# Joystick.net
KiCad netlist of a schematic drawn in EAGLE
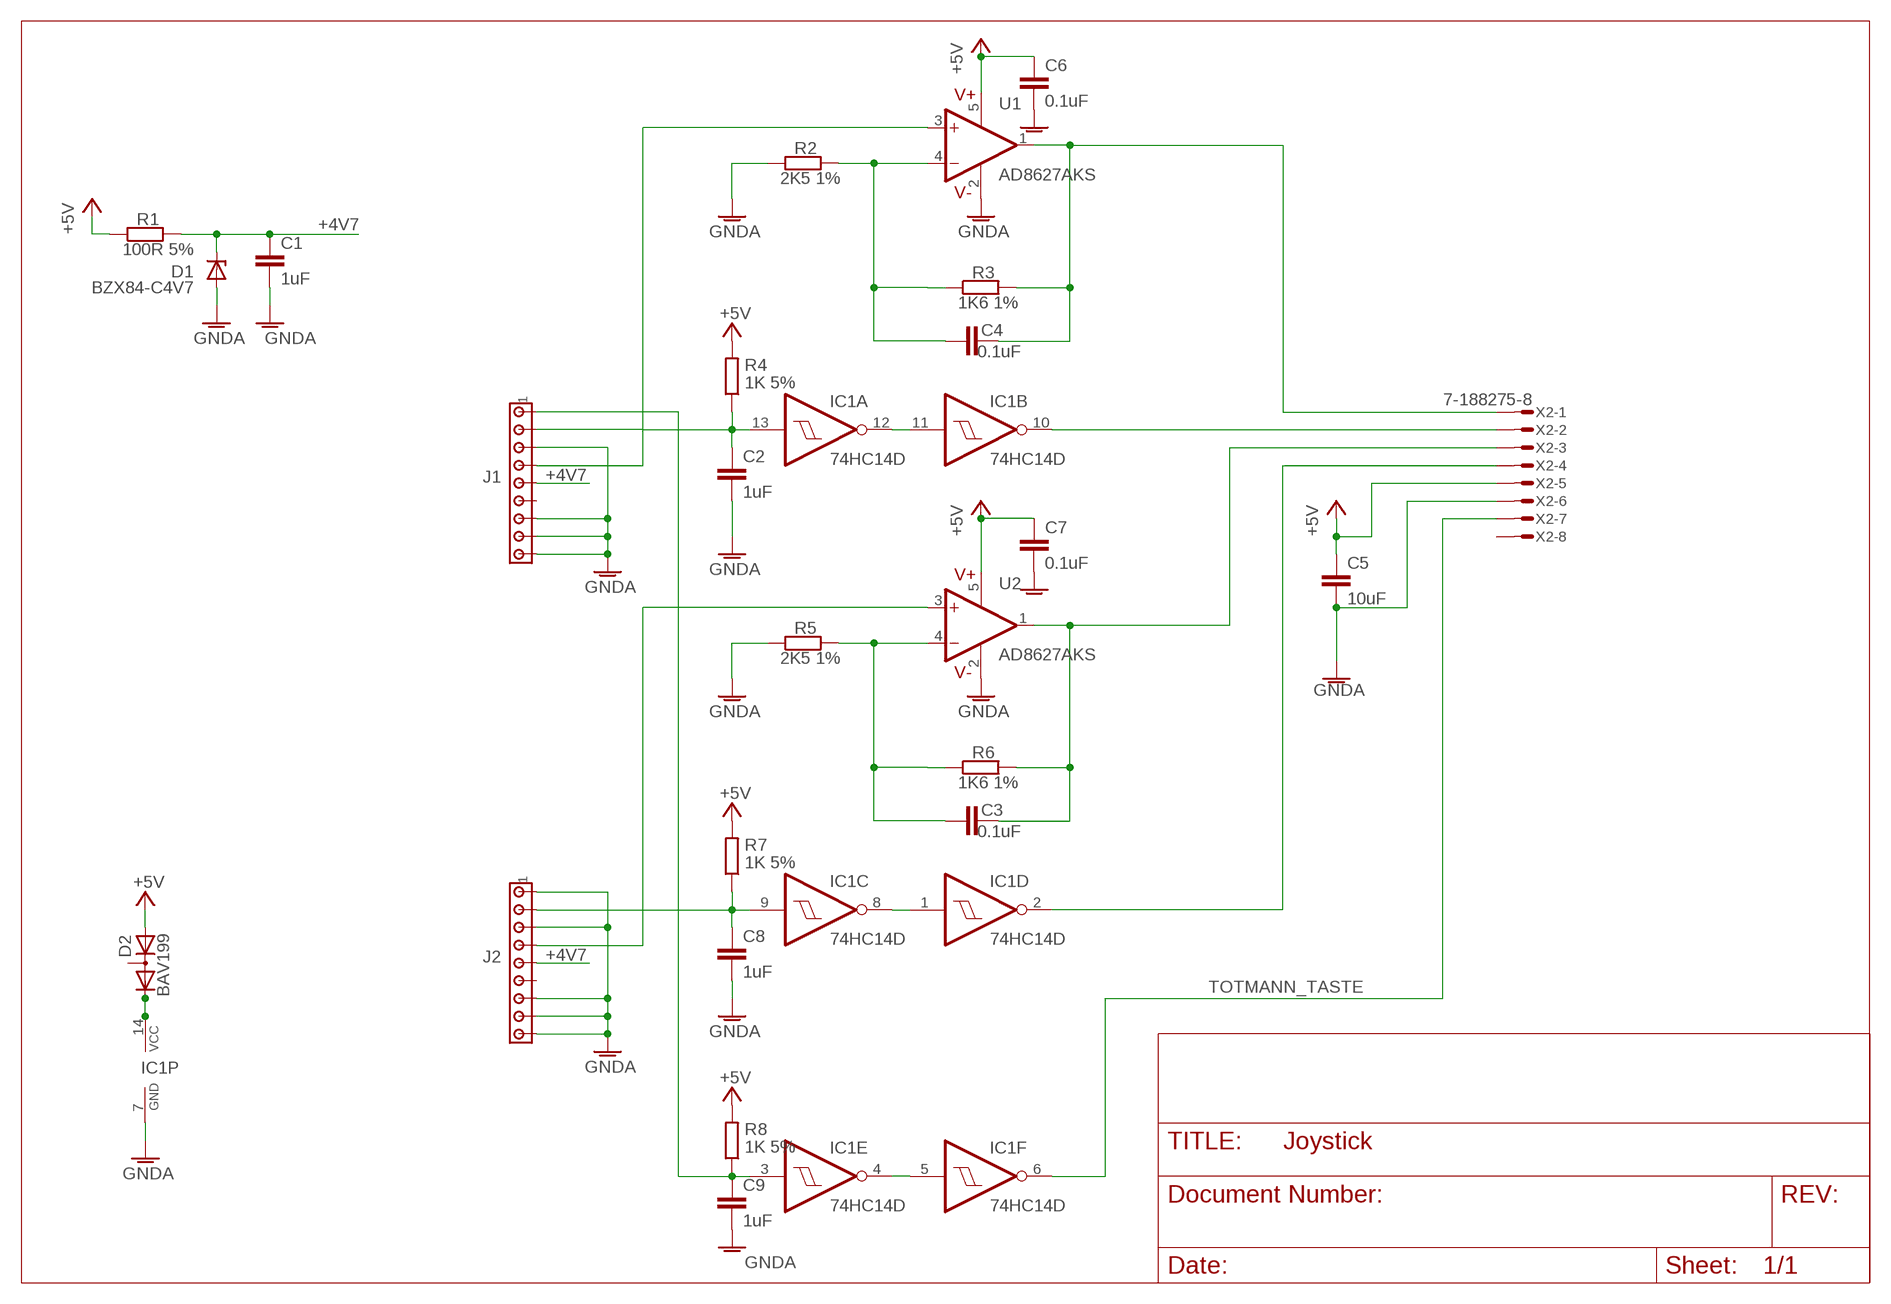
[diagram p0: schematic, sheet 1]

(export (version "E")
  (design (tool "Eeschema 10.0.6"))
  (components
    (comp (ref "C1")
      (value "1uF")
      (footprint "eagle-import:C0805")
      (libsource (lib "eagle-import") (part "C-EUC0805"))
    )
    (comp (ref "C2")
      (value "1uF")
      (footprint "eagle-import:C0805")
      (libsource (lib "eagle-import") (part "C-EUC0805"))
    )
    (comp (ref "C3")
      (value "0.1uF")
      (footprint "eagle-import:C0805")
      (libsource (lib "eagle-import") (part "C-EUC0805"))
    )
    (comp (ref "C4")
      (value "0.1uF")
      (footprint "eagle-import:C0805")
      (libsource (lib "eagle-import") (part "C-EUC0805"))
    )
    (comp (ref "C5")
      (value "10uF")
      (footprint "eagle-import:C0805")
      (libsource (lib "eagle-import") (part "C-EUC0805"))
    )
    (comp (ref "C6")
      (value "0.1uF")
      (footprint "eagle-import:C0805")
      (libsource (lib "eagle-import") (part "C-EUC0805"))
    )
    (comp (ref "C7")
      (value "0.1uF")
      (footprint "eagle-import:C0805")
      (libsource (lib "eagle-import") (part "C-EUC0805"))
    )
    (comp (ref "C8")
      (value "1uF")
      (footprint "eagle-import:C0805")
      (libsource (lib "eagle-import") (part "C-EUC0805"))
    )
    (comp (ref "C9")
      (value "1uF")
      (footprint "eagle-import:C0805")
      (libsource (lib "eagle-import") (part "C-EUC0805"))
    )
    (comp (ref "D1")
      (value "BZX84-C4V7")
      (footprint "eagle-import:SOT23")
      (libsource (lib "eagle-import") (part "ZENER-DIODESOT23"))
    )
    (comp (ref "D2")
      (value "BAV199")
      (footprint "eagle-import:SOT23")
      (libsource (lib "eagle-import") (part "BAV199"))
    )
    (comp (ref "IC1")
      (value "74HC14D")
      (footprint "eagle-import:SO14")
      (libsource (lib "eagle-import") (part "7414DHC"))
    )
    (comp (ref "J1")
      (value "MTA09-100")
      (footprint "eagle-import:10X09MTA")
      (libsource (lib "eagle-import") (part "MTA09-100"))
    )
    (comp (ref "J2")
      (value "MTA09-100")
      (footprint "eagle-import:10X09MTA")
      (libsource (lib "eagle-import") (part "MTA09-100"))
    )
    (comp (ref "R1")
      (value "100R 5%")
      (footprint "eagle-import:R0805")
      (libsource (lib "eagle-import") (part "R-EU_R0805"))
    )
    (comp (ref "R2")
      (value "2K5 1%")
      (footprint "eagle-import:R0805")
      (libsource (lib "eagle-import") (part "R-EU_R0805"))
    )
    (comp (ref "R3")
      (value "1K6 1%")
      (footprint "eagle-import:R0805")
      (libsource (lib "eagle-import") (part "R-EU_R0805"))
    )
    (comp (ref "R4")
      (value "1K 5%")
      (footprint "eagle-import:R0805")
      (libsource (lib "eagle-import") (part "R-EU_R0805"))
    )
    (comp (ref "R5")
      (value "2K5 1%")
      (footprint "eagle-import:R0805")
      (libsource (lib "eagle-import") (part "R-EU_R0805"))
    )
    (comp (ref "R6")
      (value "1K6 1%")
      (footprint "eagle-import:R0805")
      (libsource (lib "eagle-import") (part "R-EU_R0805"))
    )
    (comp (ref "R7")
      (value "1K 5%")
      (footprint "eagle-import:R0805")
      (libsource (lib "eagle-import") (part "R-EU_R0805"))
    )
    (comp (ref "R8")
      (value "1K 5%")
      (footprint "eagle-import:R0805")
      (libsource (lib "eagle-import") (part "R-EU_R0805"))
    )
    (comp (ref "U1")
      (value "AD8627AKS")
      (footprint "eagle-import:SC70(KS-5)")
      (libsource (lib "eagle-import") (part "AD8627AKS"))
    )
    (comp (ref "U2")
      (value "AD8627AKS")
      (footprint "eagle-import:SC70(KS-5)")
      (libsource (lib "eagle-import") (part "AD8627AKS"))
    )
    (comp (ref "X2")
      (value "7-188275-8")
      (footprint "eagle-import:MMT-F-SMD-8")
      (libsource (lib "eagle-import") (part "MICROMATCH-8SMF"))
    )
  )
  (nets
    (net (code "1") (name "+5V") (class "Default")
      (node (ref "C5") (pin "1") (pinfunction "1_1") (pintype "passive"))
      (node (ref "C6") (pin "1") (pinfunction "1_1") (pintype "passive"))
      (node (ref "C7") (pin "1") (pinfunction "1_1") (pintype "passive"))
      (node (ref "D2") (pin "1") (pinfunction "A_1") (pintype "passive"))
      (node (ref "R1") (pin "1") (pinfunction "1_1") (pintype "passive"))
      (node (ref "R4") (pin "2") (pinfunction "2_2") (pintype "passive"))
      (node (ref "R7") (pin "2") (pinfunction "2_2") (pintype "passive"))
      (node (ref "R8") (pin "2") (pinfunction "2_2") (pintype "passive"))
      (node (ref "U1") (pin "5") (pinfunction "V+_5") (pintype "power_in"))
      (node (ref "U2") (pin "5") (pinfunction "V+_5") (pintype "power_in"))
      (node (ref "X2") (pin "5") (pinfunction "S_5") (pintype "passive"))
    )
    (net (code "2") (name "/+4V7") (class "Default")
      (node (ref "C1") (pin "1") (pinfunction "1_1") (pintype "passive"))
      (node (ref "D1") (pin "3") (pinfunction "C_3") (pintype "passive"))
      (node (ref "J1") (pin "5") (pinfunction "5_5") (pintype "passive"))
      (node (ref "J2") (pin "5") (pinfunction "5_5") (pintype "passive"))
      (node (ref "R1") (pin "2") (pinfunction "2_2") (pintype "passive"))
    )
    (net (code "3") (name "/TOTMANN_TASTE") (class "Default")
      (node (ref "IC1") (pin "6") (pinfunction "O_6") (pintype "output"))
      (node (ref "X2") (pin "7") (pinfunction "S_7") (pintype "passive"))
    )
    (net (code "4") (name "GNDA") (class "Default")
      (node (ref "C1") (pin "2") (pinfunction "2_2") (pintype "passive"))
      (node (ref "C2") (pin "2") (pinfunction "2_2") (pintype "passive"))
      (node (ref "C5") (pin "2") (pinfunction "2_2") (pintype "passive"))
      (node (ref "C6") (pin "2") (pinfunction "2_2") (pintype "passive"))
      (node (ref "C7") (pin "2") (pinfunction "2_2") (pintype "passive"))
      (node (ref "C8") (pin "2") (pinfunction "2_2") (pintype "passive"))
      (node (ref "C9") (pin "2") (pinfunction "2_2") (pintype "passive"))
      (node (ref "D1") (pin "1") (pinfunction "A_1") (pintype "passive"))
      (node (ref "IC1") (pin "7") (pinfunction "GND_7") (pintype "power_in"))
      (node (ref "J1") (pin "3") (pinfunction "3_3") (pintype "passive"))
      (node (ref "J1") (pin "7") (pinfunction "7_7") (pintype "passive"))
      (node (ref "J1") (pin "8") (pinfunction "8_8") (pintype "passive"))
      (node (ref "J1") (pin "9") (pinfunction "9_9") (pintype "passive"))
      (node (ref "J2") (pin "1") (pinfunction "1_1") (pintype "passive"))
      (node (ref "J2") (pin "3") (pinfunction "3_3") (pintype "passive"))
      (node (ref "J2") (pin "7") (pinfunction "7_7") (pintype "passive"))
      (node (ref "J2") (pin "8") (pinfunction "8_8") (pintype "passive"))
      (node (ref "J2") (pin "9") (pinfunction "9_9") (pintype "passive"))
      (node (ref "R2") (pin "1") (pinfunction "1_1") (pintype "passive"))
      (node (ref "R5") (pin "1") (pinfunction "1_1") (pintype "passive"))
      (node (ref "U1") (pin "2") (pinfunction "V-_2") (pintype "power_in"))
      (node (ref "U2") (pin "2") (pinfunction "V-_2") (pintype "power_in"))
      (node (ref "X2") (pin "6") (pinfunction "S_6") (pintype "passive"))
    )
    (net (code "5") (name "Net-(D2-C)") (class "Default")
      (node (ref "D2") (pin "2") (pinfunction "C_2") (pintype "passive"))
      (node (ref "IC1") (pin "14") (pinfunction "VCC_14") (pintype "power_in"))
    )
    (net (code "6") (name "Net-(IC1A-I)") (class "Default")
      (node (ref "C2") (pin "1") (pinfunction "1_1") (pintype "passive"))
      (node (ref "IC1") (pin "13") (pinfunction "I_13") (pintype "input"))
      (node (ref "J1") (pin "2") (pinfunction "2_2") (pintype "passive"))
      (node (ref "R4") (pin "1") (pinfunction "1_1") (pintype "passive"))
    )
    (net (code "7") (name "Net-(IC1A-O)") (class "Default")
      (node (ref "IC1") (pin "11") (pinfunction "I_11") (pintype "input"))
      (node (ref "IC1") (pin "12") (pinfunction "O_12") (pintype "output"))
    )
    (net (code "8") (name "Net-(IC1B-O)") (class "Default")
      (node (ref "IC1") (pin "10") (pinfunction "O_10") (pintype "output"))
      (node (ref "X2") (pin "2") (pinfunction "S_2") (pintype "passive"))
    )
    (net (code "9") (name "Net-(IC1C-I)") (class "Default")
      (node (ref "C8") (pin "1") (pinfunction "1_1") (pintype "passive"))
      (node (ref "IC1") (pin "9") (pinfunction "I_9") (pintype "input"))
      (node (ref "J2") (pin "2") (pinfunction "2_2") (pintype "passive"))
      (node (ref "R7") (pin "1") (pinfunction "1_1") (pintype "passive"))
    )
    (net (code "10") (name "Net-(IC1C-O)") (class "Default")
      (node (ref "IC1") (pin "1") (pinfunction "I_1") (pintype "input"))
      (node (ref "IC1") (pin "8") (pinfunction "O_8") (pintype "output"))
    )
    (net (code "11") (name "Net-(IC1D-O)") (class "Default")
      (node (ref "IC1") (pin "2") (pinfunction "O_2") (pintype "output"))
      (node (ref "X2") (pin "4") (pinfunction "S_4") (pintype "passive"))
    )
    (net (code "12") (name "Net-(IC1E-I)") (class "Default")
      (node (ref "C9") (pin "1") (pinfunction "1_1") (pintype "passive"))
      (node (ref "IC1") (pin "3") (pinfunction "I_3") (pintype "input"))
      (node (ref "J1") (pin "1") (pinfunction "1_1") (pintype "passive"))
      (node (ref "R8") (pin "1") (pinfunction "1_1") (pintype "passive"))
    )
    (net (code "13") (name "Net-(IC1E-O)") (class "Default")
      (node (ref "IC1") (pin "4") (pinfunction "O_4") (pintype "output"))
      (node (ref "IC1") (pin "5") (pinfunction "I_5") (pintype "input"))
    )
    (net (code "14") (name "Net-(U1-+IN)") (class "Default")
      (node (ref "J1") (pin "4") (pinfunction "4_4") (pintype "passive"))
      (node (ref "U1") (pin "3") (pinfunction "+IN_3") (pintype "input"))
    )
    (net (code "15") (name "Net-(U1--IN)") (class "Default")
      (node (ref "C4") (pin "1") (pinfunction "1_1") (pintype "passive"))
      (node (ref "R2") (pin "2") (pinfunction "2_2") (pintype "passive"))
      (node (ref "R3") (pin "1") (pinfunction "1_1") (pintype "passive"))
      (node (ref "U1") (pin "4") (pinfunction "-IN_4") (pintype "input"))
    )
    (net (code "16") (name "Net-(U1-OUT)") (class "Default")
      (node (ref "C4") (pin "2") (pinfunction "2_2") (pintype "passive"))
      (node (ref "R3") (pin "2") (pinfunction "2_2") (pintype "passive"))
      (node (ref "U1") (pin "1") (pinfunction "OUT_1") (pintype "output"))
      (node (ref "X2") (pin "1") (pinfunction "S_1") (pintype "passive"))
    )
    (net (code "17") (name "Net-(U2-+IN)") (class "Default")
      (node (ref "J2") (pin "4") (pinfunction "4_4") (pintype "passive"))
      (node (ref "U2") (pin "3") (pinfunction "+IN_3") (pintype "input"))
    )
    (net (code "18") (name "Net-(U2--IN)") (class "Default")
      (node (ref "C3") (pin "1") (pinfunction "1_1") (pintype "passive"))
      (node (ref "R5") (pin "2") (pinfunction "2_2") (pintype "passive"))
      (node (ref "R6") (pin "1") (pinfunction "1_1") (pintype "passive"))
      (node (ref "U2") (pin "4") (pinfunction "-IN_4") (pintype "input"))
    )
    (net (code "19") (name "Net-(U2-OUT)") (class "Default")
      (node (ref "C3") (pin "2") (pinfunction "2_2") (pintype "passive"))
      (node (ref "R6") (pin "2") (pinfunction "2_2") (pintype "passive"))
      (node (ref "U2") (pin "1") (pinfunction "OUT_1") (pintype "output"))
      (node (ref "X2") (pin "3") (pinfunction "S_3") (pintype "passive"))
    )
    (net (code "20") (name "unconnected-(D2-AC-Pad3)") (class "Default")
      (node (ref "D2") (pin "3") (pinfunction "AC_3") (pintype "passive"))
    )
    (net (code "21") (name "unconnected-(J1-Pad6)") (class "Default")
      (node (ref "J1") (pin "6") (pinfunction "6_6") (pintype "passive"))
    )
    (net (code "22") (name "unconnected-(J2-Pad6)") (class "Default")
      (node (ref "J2") (pin "6") (pinfunction "6_6") (pintype "passive"))
    )
    (net (code "23") (name "unconnected-(X2H-S-Pad8)") (class "Default")
      (node (ref "X2") (pin "8") (pinfunction "S_8") (pintype "passive"))
    )
  )
)
